# MCU.net
KiCad netlist of a schematic drawn in Altium Designer
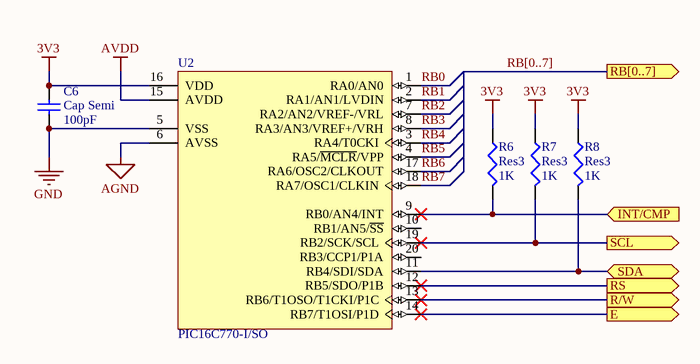
[diagram p0: MCU.SchDoc]

(export (version "E")
  (design (tool "Eeschema 10.0.6"))
  (components
    (comp (ref "C6")
      (value "Cap Semi")
      (footprint "0603_C")
      (description "Capacitor (Semiconductor SIM Model)")
      (fields (field (name "ALTIUM_VALUE") "100pF") (field (name "PUBLISHER") "Altium Limited"))
      (libsource (lib "Miscellaneous Devices") (part "Cap Semi"))
    )
    (comp (ref "R6")
      (value "Res3")
      (footprint "0603_R")
      (description "Resistor")
      (fields (field (name "ALTIUM_VALUE") "1K") (field (name "PUBLISHER") "Altium Limited"))
      (libsource (lib "Miscellaneous Devices") (part "Res3"))
    )
    (comp (ref "R7")
      (value "Res3")
      (footprint "0603_R")
      (description "Resistor")
      (fields (field (name "ALTIUM_VALUE") "1K") (field (name "PUBLISHER") "Altium Limited"))
      (libsource (lib "Miscellaneous Devices") (part "Res3"))
    )
    (comp (ref "R8")
      (value "Res3")
      (footprint "0603_R")
      (description "Resistor")
      (fields (field (name "ALTIUM_VALUE") "1K") (field (name "PUBLISHER") "Altium Limited"))
      (libsource (lib "Miscellaneous Devices") (part "Res3"))
    )
    (comp (ref "U2")
      (value "PIC16C770-I/SO")
      (footprint "SOIC-20_300mil")
      (fields (field (name "PUBLISHER") "Altium Limited"))
      (libsource (lib "Microchip Microcontroller 8-Bit PIC16") (part "PIC16C770-I/SO"))
    )
  )
  (nets
    (net (code "1") (name "/E") (class "Default")
      (node (ref "U2") (pin "14") (pinfunction "RB7/T1OSI/P1D_14") (pintype "bidirectional+no_connect"))
    )
    (net (code "2") (name "/INT{slash}CMP") (class "Default")
      (node (ref "R6") (pin "2") (pinfunction "2_2") (pintype "passive"))
      (node (ref "U2") (pin "9") (pinfunction "RB0/AN4/INT_9") (pintype "bidirectional"))
    )
    (net (code "3") (name "/RB0") (class "Default")
      (node (ref "U2") (pin "1") (pinfunction "RA0/AN0_1") (pintype "bidirectional"))
    )
    (net (code "4") (name "/RB1") (class "Default")
      (node (ref "U2") (pin "2") (pinfunction "RA1/AN1/LVDIN_2") (pintype "bidirectional"))
    )
    (net (code "5") (name "/RB2") (class "Default")
      (node (ref "U2") (pin "7") (pinfunction "RA2/AN2/VREF-/VRL_7") (pintype "bidirectional"))
    )
    (net (code "6") (name "/RB3") (class "Default")
      (node (ref "U2") (pin "8") (pinfunction "RA3/AN3/VREF+/VRH_8") (pintype "bidirectional"))
    )
    (net (code "7") (name "/RB4") (class "Default")
      (node (ref "U2") (pin "3") (pinfunction "RA4/T0CKI_3") (pintype "bidirectional"))
    )
    (net (code "8") (name "/RB5") (class "Default")
      (node (ref "U2") (pin "4") (pinfunction "RA5/~{MCLR}/VPP_4") (pintype "bidirectional"))
    )
    (net (code "9") (name "/RB6") (class "Default")
      (node (ref "U2") (pin "17") (pinfunction "RA6/OSC2/CLKOUT_17") (pintype "bidirectional"))
    )
    (net (code "10") (name "/RB7") (class "Default")
      (node (ref "U2") (pin "18") (pinfunction "RA7/OSC1/CLKIN_18") (pintype "bidirectional"))
    )
    (net (code "12") (name "/RS") (class "Default")
      (node (ref "U2") (pin "12") (pinfunction "RB5/SDO/P1B_12") (pintype "bidirectional+no_connect"))
    )
    (net (code "13") (name "/R{slash}W") (class "Default")
      (node (ref "U2") (pin "13") (pinfunction "RB6/T1OSO/T1CKI/P1C_13") (pintype "bidirectional+no_connect"))
    )
    (net (code "14") (name "/SCL") (class "Default")
      (node (ref "R7") (pin "2") (pinfunction "2_2") (pintype "passive"))
      (node (ref "U2") (pin "19") (pinfunction "RB2/SCK/SCL_19") (pintype "bidirectional"))
    )
    (net (code "15") (name "/SDA") (class "Default")
      (node (ref "R8") (pin "2") (pinfunction "2_2") (pintype "passive"))
      (node (ref "U2") (pin "11") (pinfunction "RB4/SDI/SDA_11") (pintype "bidirectional"))
    )
    (net (code "16") (name "3V3") (class "Default")
      (node (ref "C6") (pin "2") (pinfunction "2_2") (pintype "passive"))
      (node (ref "R6") (pin "1") (pinfunction "1_1") (pintype "passive"))
      (node (ref "R7") (pin "1") (pinfunction "1_1") (pintype "passive"))
      (node (ref "R8") (pin "1") (pinfunction "1_1") (pintype "passive"))
      (node (ref "U2") (pin "16") (pinfunction "VDD_16") (pintype "power_in"))
    )
    (net (code "17") (name "AGND") (class "Default")
      (node (ref "U2") (pin "6") (pinfunction "AVSS_6") (pintype "power_in"))
    )
    (net (code "18") (name "AVDD") (class "Default")
      (node (ref "U2") (pin "15") (pinfunction "AVDD_15") (pintype "power_in"))
    )
    (net (code "19") (name "GND") (class "Default")
      (node (ref "C6") (pin "1") (pinfunction "1_1") (pintype "passive"))
      (node (ref "U2") (pin "5") (pinfunction "VSS_5") (pintype "power_in"))
    )
    (net (code "20") (name "unconnected-(U2-RB1{slash}AN5{slash}~{SS}-Pad10)") (class "Default")
      (node (ref "U2") (pin "10") (pinfunction "RB1/AN5/~{SS}_10") (pintype "bidirectional"))
    )
    (net (code "21") (name "unconnected-(U2-RB3{slash}CCP1{slash}P1A-Pad20)") (class "Default")
      (node (ref "U2") (pin "20") (pinfunction "RB3/CCP1/P1A_20") (pintype "bidirectional"))
    )
  )
)
